# PSU_VCC1V8AUX_Buck.net
KiCad netlist of a schematic drawn in Altium Designer
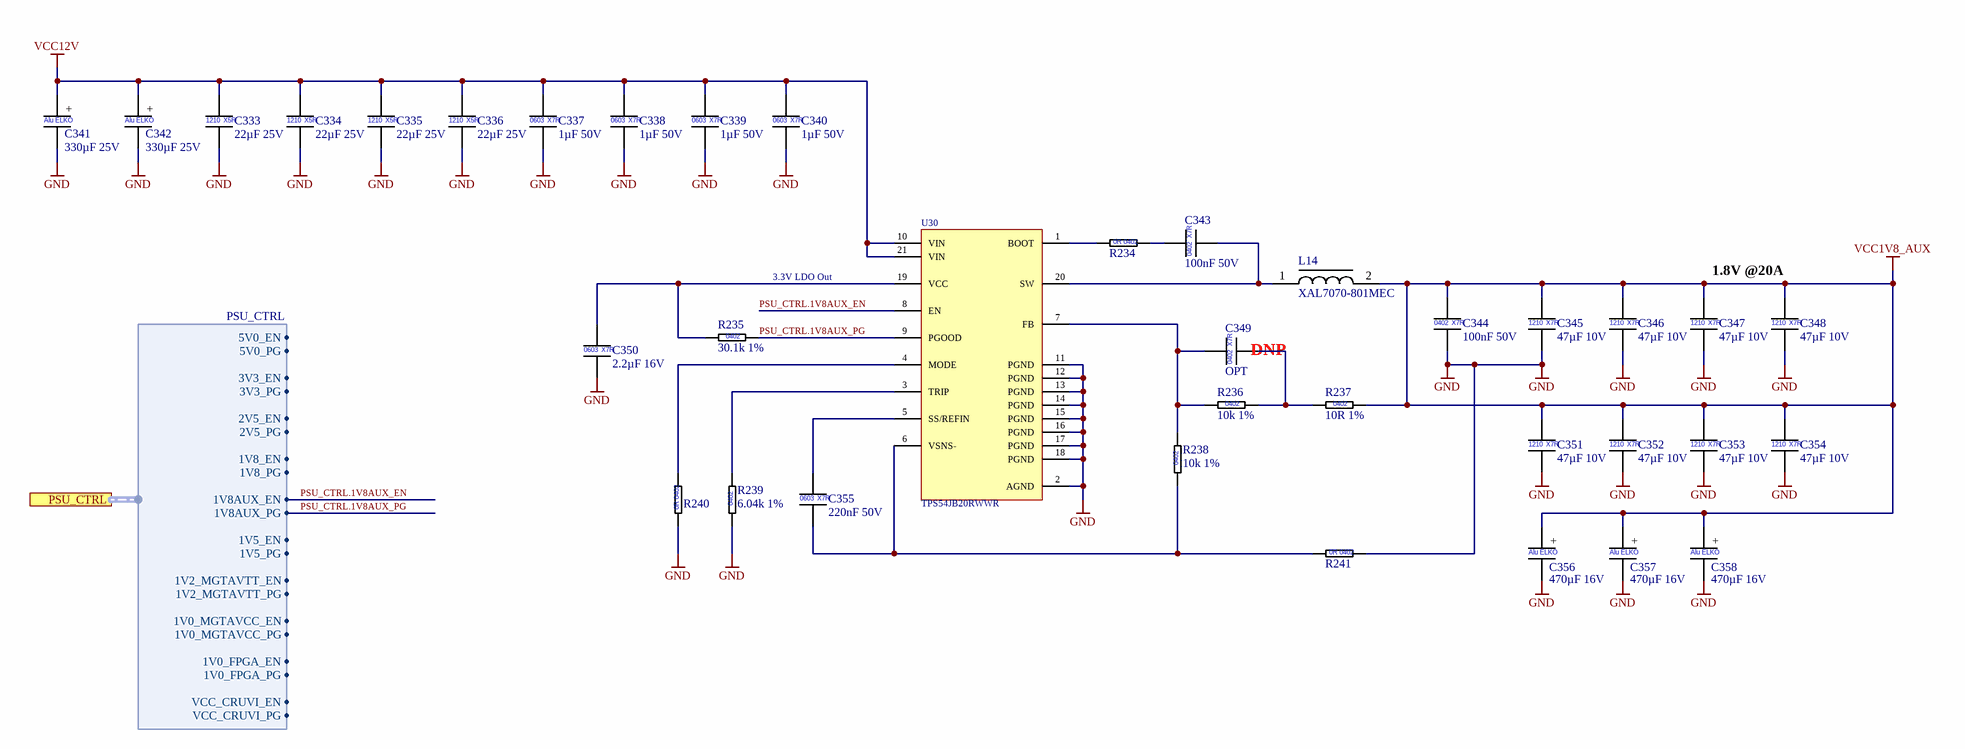
[diagram p0: PSU_VCC1V8AUX_Buck.SchDoc]

(export (version "E")
  (design (tool "Eeschema 10.0.6"))
  (components
    (comp (ref "C333")
      (value "22µF 25V")
      (footprint "Cap:CAP_1210")
      (description "Multilayer Ceramic Capacitors MLCC - SMD/SMT 1210 25VDC")
      (libsource (lib "Cap") (part "CAP_1210_22µF_25V"))
    )
    (comp (ref "C334")
      (value "22µF 25V")
      (footprint "Cap:CAP_1210")
      (description "Multilayer Ceramic Capacitors MLCC - SMD/SMT 1210 25VDC")
      (libsource (lib "Cap") (part "CAP_1210_22µF_25V"))
    )
    (comp (ref "C335")
      (value "22µF 25V")
      (footprint "Cap:CAP_1210")
      (description "Multilayer Ceramic Capacitors MLCC - SMD/SMT 1210 25VDC")
      (libsource (lib "Cap") (part "CAP_1210_22µF_25V"))
    )
    (comp (ref "C336")
      (value "22µF 25V")
      (footprint "Cap:CAP_1210")
      (description "Multilayer Ceramic Capacitors MLCC - SMD/SMT 1210 25VDC")
      (libsource (lib "Cap") (part "CAP_1210_22µF_25V"))
    )
    (comp (ref "C337")
      (value "1µF 50V")
      (footprint "CAP_0603")
      (description "Multilayer Ceramic Capacitors MLCC - SMD/SMT 50V 1uF X7R 0603 10%")
      (libsource (lib "Cap") (part "CAP_0603_1µF_50V_X7R_10%"))
    )
    (comp (ref "C338")
      (value "1µF 50V")
      (footprint "CAP_0603")
      (description "Multilayer Ceramic Capacitors MLCC - SMD/SMT 50V 1uF X7R 0603 10%")
      (libsource (lib "Cap") (part "CAP_0603_1µF_50V_X7R_10%"))
    )
    (comp (ref "C339")
      (value "1µF 50V")
      (footprint "CAP_0603")
      (description "Multilayer Ceramic Capacitors MLCC - SMD/SMT 50V 1uF X7R 0603 10%")
      (libsource (lib "Cap") (part "CAP_0603_1µF_50V_X7R_10%"))
    )
    (comp (ref "C340")
      (value "1µF 50V")
      (footprint "CAP_0603")
      (description "Multilayer Ceramic Capacitors MLCC - SMD/SMT 50V 1uF X7R 0603 10%")
      (libsource (lib "Cap") (part "CAP_0603_1µF_50V_X7R_10%"))
    )
    (comp (ref "C341")
      (value "330µF 25V")
      (footprint "Cap:WCAP-PTG5_D10H12.5")
      (description "Organische Polymer-Aluminiumkondensatoren 330uF 25 Volts 20% AEC-Q200")
      (libsource (lib "Cap") (part "CAP_D10L12.5_330µF_25V"))
    )
    (comp (ref "C342")
      (value "330µF 25V")
      (footprint "Cap:WCAP-PTG5_D10H12.5")
      (description "Organische Polymer-Aluminiumkondensatoren 330uF 25 Volts 20% AEC-Q200")
      (libsource (lib "Cap") (part "CAP_D10L12.5_330µF_25V"))
    )
    (comp (ref "C343")
      (value "100nF 50V")
      (footprint "Cap:CAP_0402")
      (description "Multilayer Ceramic Capacitors MLCC - SMD/SMT 0402 50VDC")
      (libsource (lib "") (part "CAP_0402_100nF_50V_1"))
    )
    (comp (ref "C344")
      (value "100nF 50V")
      (footprint "Cap:CAP_0402")
      (description "Multilayer Ceramic Capacitors MLCC - SMD/SMT 0402 50VDC")
      (libsource (lib "Cap") (part "CAP_0402_100nF_50V"))
    )
    (comp (ref "C345")
      (value "47µF 10V")
      (footprint "Cap:CAP_1210")
      (description "Multilayer Ceramic Capacitors MLCC - SMD/SMT 47 uF 10 VDC 10% 1210 X7R")
      (libsource (lib "Cap") (part "CAP_1210_47µF_10V_X7R_10%"))
    )
    (comp (ref "C346")
      (value "47µF 10V")
      (footprint "Cap:CAP_1210")
      (description "Multilayer Ceramic Capacitors MLCC - SMD/SMT 47 uF 10 VDC 10% 1210 X7R")
      (libsource (lib "Cap") (part "CAP_1210_47µF_10V_X7R_10%"))
    )
    (comp (ref "C347")
      (value "47µF 10V")
      (footprint "Cap:CAP_1210")
      (description "Multilayer Ceramic Capacitors MLCC - SMD/SMT 47 uF 10 VDC 10% 1210 X7R")
      (libsource (lib "Cap") (part "CAP_1210_47µF_10V_X7R_10%"))
    )
    (comp (ref "C348")
      (value "47µF 10V")
      (footprint "Cap:CAP_1210")
      (description "Multilayer Ceramic Capacitors MLCC - SMD/SMT 47 uF 10 VDC 10% 1210 X7R")
      (libsource (lib "Cap") (part "CAP_1210_47µF_10V_X7R_10%"))
    )
    (comp (ref "C349")
      (value "OPT")
      (footprint "Cap:CAP_0402")
      (description "Multilayer Ceramic Capacitors MLCC - SMD/SMT 0402 Optional Placeholder")
      (libsource (lib "Cap") (part "CAP_0402_OPT"))
    )
    (comp (ref "C350")
      (value "2.2µF 16V")
      (footprint "Cap:CAP_0603")
      (description "Multilayer Ceramic Capacitors MLCC - SMD/SMT 2.2 uF 16 VDC 10% 0603 X7R")
      (libsource (lib "Cap") (part "CAP_0603_2.2µF_16V_X7R_10%"))
    )
    (comp (ref "C351")
      (value "47µF 10V")
      (footprint "Cap:CAP_1210")
      (description "Multilayer Ceramic Capacitors MLCC - SMD/SMT 47 uF 10 VDC 10% 1210 X7R")
      (libsource (lib "Cap") (part "CAP_1210_47µF_10V_X7R_10%"))
    )
    (comp (ref "C352")
      (value "47µF 10V")
      (footprint "Cap:CAP_1210")
      (description "Multilayer Ceramic Capacitors MLCC - SMD/SMT 47 uF 10 VDC 10% 1210 X7R")
      (libsource (lib "Cap") (part "CAP_1210_47µF_10V_X7R_10%"))
    )
    (comp (ref "C353")
      (value "47µF 10V")
      (footprint "Cap:CAP_1210")
      (description "Multilayer Ceramic Capacitors MLCC - SMD/SMT 47 uF 10 VDC 10% 1210 X7R")
      (libsource (lib "Cap") (part "CAP_1210_47µF_10V_X7R_10%"))
    )
    (comp (ref "C354")
      (value "47µF 10V")
      (footprint "Cap:CAP_1210")
      (description "Multilayer Ceramic Capacitors MLCC - SMD/SMT 47 uF 10 VDC 10% 1210 X7R")
      (libsource (lib "Cap") (part "CAP_1210_47µF_10V_X7R_10%"))
    )
    (comp (ref "C355")
      (value "220nF 50V")
      (footprint "CAP_0603")
      (description "Multilayer Ceramic Capacitors MLCC - SMD/SMT 0.22 uF 50 VDC 10% 0603 X7R")
      (libsource (lib "Cap") (part "CAP_0603_220nF_50V_X7R_10%"))
    )
    (comp (ref "C356")
      (value "470µF 16V")
      (footprint "Cap:WCAP-PTG5_D8H13")
      (description "Organische Polymer-Aluminiumkondensatoren 470uF 16 Volts 20%")
      (libsource (lib "Cap") (part "CAP_D8L9_470µF_16V"))
    )
    (comp (ref "C357")
      (value "470µF 16V")
      (footprint "Cap:WCAP-PTG5_D8H13")
      (description "Organische Polymer-Aluminiumkondensatoren 470uF 16 Volts 20%")
      (libsource (lib "Cap") (part "CAP_D8L9_470µF_16V"))
    )
    (comp (ref "C358")
      (value "470µF 16V")
      (footprint "Cap:WCAP-PTG5_D8H13")
      (description "Organische Polymer-Aluminiumkondensatoren 470uF 16 Volts 20%")
      (libsource (lib "Cap") (part "CAP_D8L9_470µF_16V"))
    )
    (comp (ref "L14")
      (value "XAL7070-801MEC")
      (footprint "indc:COILCRAFT_XAL7070")
      (description "Power Inductors - SMD 800nH Shld 20% 25.8A 2.29mOhms AECQ200")
      (libsource (lib "Indc") (part "XAL7070-801MEC_Power Inductors SMD 800nH Shld 20% 25.8A 2.29mOhms AECQ200"))
    )
    (comp (ref "R234")
      (value "0R Jumper")
      (footprint "res:RES_0402")
      (description "Thick Film Resistors - SMD 0Ohm")
      (libsource (lib "Res") (part "RES_0402_0R Jumper"))
    )
    (comp (ref "R235")
      (value "30.1k 1%")
      (footprint "res:RES_0402")
      (description "Thick Film Resistors - SMD 30.1kOhm 1%")
      (libsource (lib "Res") (part "RES_0402_30.1k_1%"))
    )
    (comp (ref "R236")
      (value "10k 1%")
      (footprint "Res:RES_0402")
      (description "Thick Film Resistors - SMD 10kOhm 1%")
      (libsource (lib "Res") (part "RES_0402_10k_1%"))
    )
    (comp (ref "R237")
      (value "10R 1%")
      (footprint "res:RES_0402")
      (description "Thick Film Resistors - SMD 10Ohm 1%")
      (libsource (lib "Res") (part "RES_0402_10R_1%"))
    )
    (comp (ref "R238")
      (value "10k 1%")
      (footprint "Res:RES_0402")
      (description "Thick Film Resistors - SMD 10kOhm 1%")
      (libsource (lib "Res") (part "RES_0402_10k_1%"))
    )
    (comp (ref "R239")
      (value "6.04k 1%")
      (footprint "Res:RES_0402")
      (description "Thick Film Resistors - SMD 6.04kOhm 1%")
      (libsource (lib "Res") (part "RES_0402_6.04k_1%"))
    )
    (comp (ref "R240")
      (value "0R Jumper")
      (footprint "res:RES_0402")
      (description "Thick Film Resistors - SMD 0Ohm")
      (libsource (lib "Res") (part "RES_0402_0R Jumper"))
    )
    (comp (ref "R241")
      (value "0R Jumper")
      (footprint "res:RES_0402")
      (description "Thick Film Resistors - SMD 0Ohm")
      (libsource (lib "Res") (part "RES_0402_0R Jumper"))
    )
    (comp (ref "U30")
      (value "TPS54JB20RWWR")
      (footprint "power:VQFN-HR21_RWW0021A")
      (description "Switching Voltage Regulators 2.7-V to 16-V input 20-A synchronous Buck")
      (libsource (lib "Power") (part "TPS54JB20RWWR_Switching Voltage Regulators 2.7-V to 16-V input 20-A synchronous Buck"))
    )
  )
  (nets
    (net (code "2") (name "/PSU_CTRL.1V8AUX_EN") (class "Default")
      (node (ref "U30") (pin "8") (pinfunction "EN_8") (pintype "passive"))
    )
    (net (code "3") (name "/PSU_CTRL.1V8AUX_PG") (class "Default")
      (node (ref "R235") (pin "2") (pinfunction "2_2") (pintype "passive"))
      (node (ref "U30") (pin "9") (pinfunction "PGOOD_9") (pintype "passive"))
    )
    (net (code "5") (name "GND") (class "Default")
      (node (ref "C333") (pin "2") (pinfunction "2_2") (pintype "passive"))
      (node (ref "C334") (pin "2") (pinfunction "2_2") (pintype "passive"))
      (node (ref "C335") (pin "2") (pinfunction "2_2") (pintype "passive"))
      (node (ref "C336") (pin "2") (pinfunction "2_2") (pintype "passive"))
      (node (ref "C337") (pin "2") (pinfunction "2_2") (pintype "passive"))
      (node (ref "C338") (pin "2") (pinfunction "2_2") (pintype "passive"))
      (node (ref "C339") (pin "2") (pinfunction "2_2") (pintype "passive"))
      (node (ref "C340") (pin "2") (pinfunction "2_2") (pintype "passive"))
      (node (ref "C341") (pin "2") (pinfunction "2_2") (pintype "passive"))
      (node (ref "C342") (pin "2") (pinfunction "2_2") (pintype "passive"))
      (node (ref "C344") (pin "2") (pinfunction "2_2") (pintype "passive"))
      (node (ref "C345") (pin "2") (pinfunction "2_2") (pintype "passive"))
      (node (ref "C346") (pin "2") (pinfunction "2_2") (pintype "passive"))
      (node (ref "C347") (pin "2") (pinfunction "2_2") (pintype "passive"))
      (node (ref "C348") (pin "2") (pinfunction "2_2") (pintype "passive"))
      (node (ref "C350") (pin "2") (pinfunction "2_2") (pintype "passive"))
      (node (ref "C351") (pin "2") (pinfunction "2_2") (pintype "passive"))
      (node (ref "C352") (pin "2") (pinfunction "2_2") (pintype "passive"))
      (node (ref "C353") (pin "2") (pinfunction "2_2") (pintype "passive"))
      (node (ref "C354") (pin "2") (pinfunction "2_2") (pintype "passive"))
      (node (ref "C356") (pin "2") (pinfunction "2_2") (pintype "passive"))
      (node (ref "C357") (pin "2") (pinfunction "2_2") (pintype "passive"))
      (node (ref "C358") (pin "2") (pinfunction "2_2") (pintype "passive"))
      (node (ref "R239") (pin "1") (pinfunction "1_1") (pintype "passive"))
      (node (ref "R240") (pin "1") (pinfunction "1_1") (pintype "passive"))
      (node (ref "R241") (pin "2") (pinfunction "2_2") (pintype "passive"))
      (node (ref "U30") (pin "11") (pinfunction "PGND_11") (pintype "passive"))
      (node (ref "U30") (pin "12") (pinfunction "PGND_12") (pintype "passive"))
      (node (ref "U30") (pin "13") (pinfunction "PGND_13") (pintype "passive"))
      (node (ref "U30") (pin "14") (pinfunction "PGND_14") (pintype "passive"))
      (node (ref "U30") (pin "15") (pinfunction "PGND_15") (pintype "passive"))
      (node (ref "U30") (pin "16") (pinfunction "PGND_16") (pintype "passive"))
      (node (ref "U30") (pin "17") (pinfunction "PGND_17") (pintype "passive"))
      (node (ref "U30") (pin "18") (pinfunction "PGND_18") (pintype "passive"))
      (node (ref "U30") (pin "2") (pinfunction "AGND_2") (pintype "passive"))
    )
    (net (code "6") (name "Net-(C343-Pad1)") (class "Default")
      (node (ref "C343") (pin "1") (pinfunction "1_1") (pintype "passive"))
      (node (ref "R234") (pin "2") (pinfunction "2_2") (pintype "passive"))
    )
    (net (code "7") (name "Net-(C349-Pad2)") (class "Default")
      (node (ref "C349") (pin "2") (pinfunction "2_2") (pintype "passive"))
      (node (ref "R236") (pin "2") (pinfunction "2_2") (pintype "passive"))
      (node (ref "R237") (pin "1") (pinfunction "1_1") (pintype "passive"))
    )
    (net (code "8") (name "Net-(U30-BOOT)") (class "Default")
      (node (ref "R234") (pin "1") (pinfunction "1_1") (pintype "passive"))
      (node (ref "U30") (pin "1") (pinfunction "BOOT_1") (pintype "passive"))
    )
    (net (code "9") (name "Net-(U30-FB)") (class "Default")
      (node (ref "C349") (pin "1") (pinfunction "1_1") (pintype "passive"))
      (node (ref "R236") (pin "1") (pinfunction "1_1") (pintype "passive"))
      (node (ref "R238") (pin "2") (pinfunction "2_2") (pintype "passive"))
      (node (ref "U30") (pin "7") (pinfunction "FB_7") (pintype "passive"))
    )
    (net (code "10") (name "Net-(U30-MODE)") (class "Default")
      (node (ref "R240") (pin "2") (pinfunction "2_2") (pintype "passive"))
      (node (ref "U30") (pin "4") (pinfunction "MODE_4") (pintype "passive"))
    )
    (net (code "11") (name "Net-(U30-SS{slash}REFIN)") (class "Default")
      (node (ref "C355") (pin "1") (pinfunction "1_1") (pintype "passive"))
      (node (ref "U30") (pin "5") (pinfunction "SS/REFIN_5") (pintype "passive"))
    )
    (net (code "12") (name "Net-(U30-SW)") (class "Default")
      (node (ref "C343") (pin "2") (pinfunction "2_2") (pintype "passive"))
      (node (ref "L14") (pin "1") (pinfunction "1_1") (pintype "passive"))
      (node (ref "U30") (pin "20") (pinfunction "SW_20") (pintype "passive"))
    )
    (net (code "13") (name "Net-(U30-TRIP)") (class "Default")
      (node (ref "R239") (pin "2") (pinfunction "2_2") (pintype "passive"))
      (node (ref "U30") (pin "3") (pinfunction "TRIP_3") (pintype "passive"))
    )
    (net (code "14") (name "Net-(U30-VCC)") (class "Default")
      (node (ref "C350") (pin "1") (pinfunction "1_1") (pintype "passive"))
      (node (ref "R235") (pin "1") (pinfunction "1_1") (pintype "passive"))
      (node (ref "U30") (pin "19") (pinfunction "VCC_19") (pintype "passive"))
    )
    (net (code "15") (name "Net-(U30-VSNS-)") (class "Default")
      (node (ref "C355") (pin "2") (pinfunction "2_2") (pintype "passive"))
      (node (ref "R238") (pin "1") (pinfunction "1_1") (pintype "passive"))
      (node (ref "R241") (pin "1") (pinfunction "1_1") (pintype "passive"))
      (node (ref "U30") (pin "6") (pinfunction "VSNS-_6") (pintype "passive"))
    )
    (net (code "16") (name "VCC1V8_AUX") (class "Default")
      (node (ref "C344") (pin "1") (pinfunction "1_1") (pintype "passive"))
      (node (ref "C345") (pin "1") (pinfunction "1_1") (pintype "passive"))
      (node (ref "C346") (pin "1") (pinfunction "1_1") (pintype "passive"))
      (node (ref "C347") (pin "1") (pinfunction "1_1") (pintype "passive"))
      (node (ref "C348") (pin "1") (pinfunction "1_1") (pintype "passive"))
      (node (ref "C351") (pin "1") (pinfunction "1_1") (pintype "passive"))
      (node (ref "C352") (pin "1") (pinfunction "1_1") (pintype "passive"))
      (node (ref "C353") (pin "1") (pinfunction "1_1") (pintype "passive"))
      (node (ref "C354") (pin "1") (pinfunction "1_1") (pintype "passive"))
      (node (ref "C356") (pin "1") (pinfunction "1_1") (pintype "passive"))
      (node (ref "C357") (pin "1") (pinfunction "1_1") (pintype "passive"))
      (node (ref "C358") (pin "1") (pinfunction "1_1") (pintype "passive"))
      (node (ref "L14") (pin "2") (pinfunction "2_2") (pintype "passive"))
      (node (ref "R237") (pin "2") (pinfunction "2_2") (pintype "passive"))
    )
    (net (code "17") (name "VCC12V") (class "Default")
      (node (ref "C333") (pin "1") (pinfunction "1_1") (pintype "passive"))
      (node (ref "C334") (pin "1") (pinfunction "1_1") (pintype "passive"))
      (node (ref "C335") (pin "1") (pinfunction "1_1") (pintype "passive"))
      (node (ref "C336") (pin "1") (pinfunction "1_1") (pintype "passive"))
      (node (ref "C337") (pin "1") (pinfunction "1_1") (pintype "passive"))
      (node (ref "C338") (pin "1") (pinfunction "1_1") (pintype "passive"))
      (node (ref "C339") (pin "1") (pinfunction "1_1") (pintype "passive"))
      (node (ref "C340") (pin "1") (pinfunction "1_1") (pintype "passive"))
      (node (ref "C341") (pin "1") (pinfunction "1_1") (pintype "passive"))
      (node (ref "C342") (pin "1") (pinfunction "1_1") (pintype "passive"))
      (node (ref "U30") (pin "10") (pinfunction "VIN_10") (pintype "passive"))
      (node (ref "U30") (pin "21") (pinfunction "VIN_21") (pintype "passive"))
    )
  )
)
